# DM0249_IMX378.net
KiCad netlist of a schematic drawn in Altium Designer
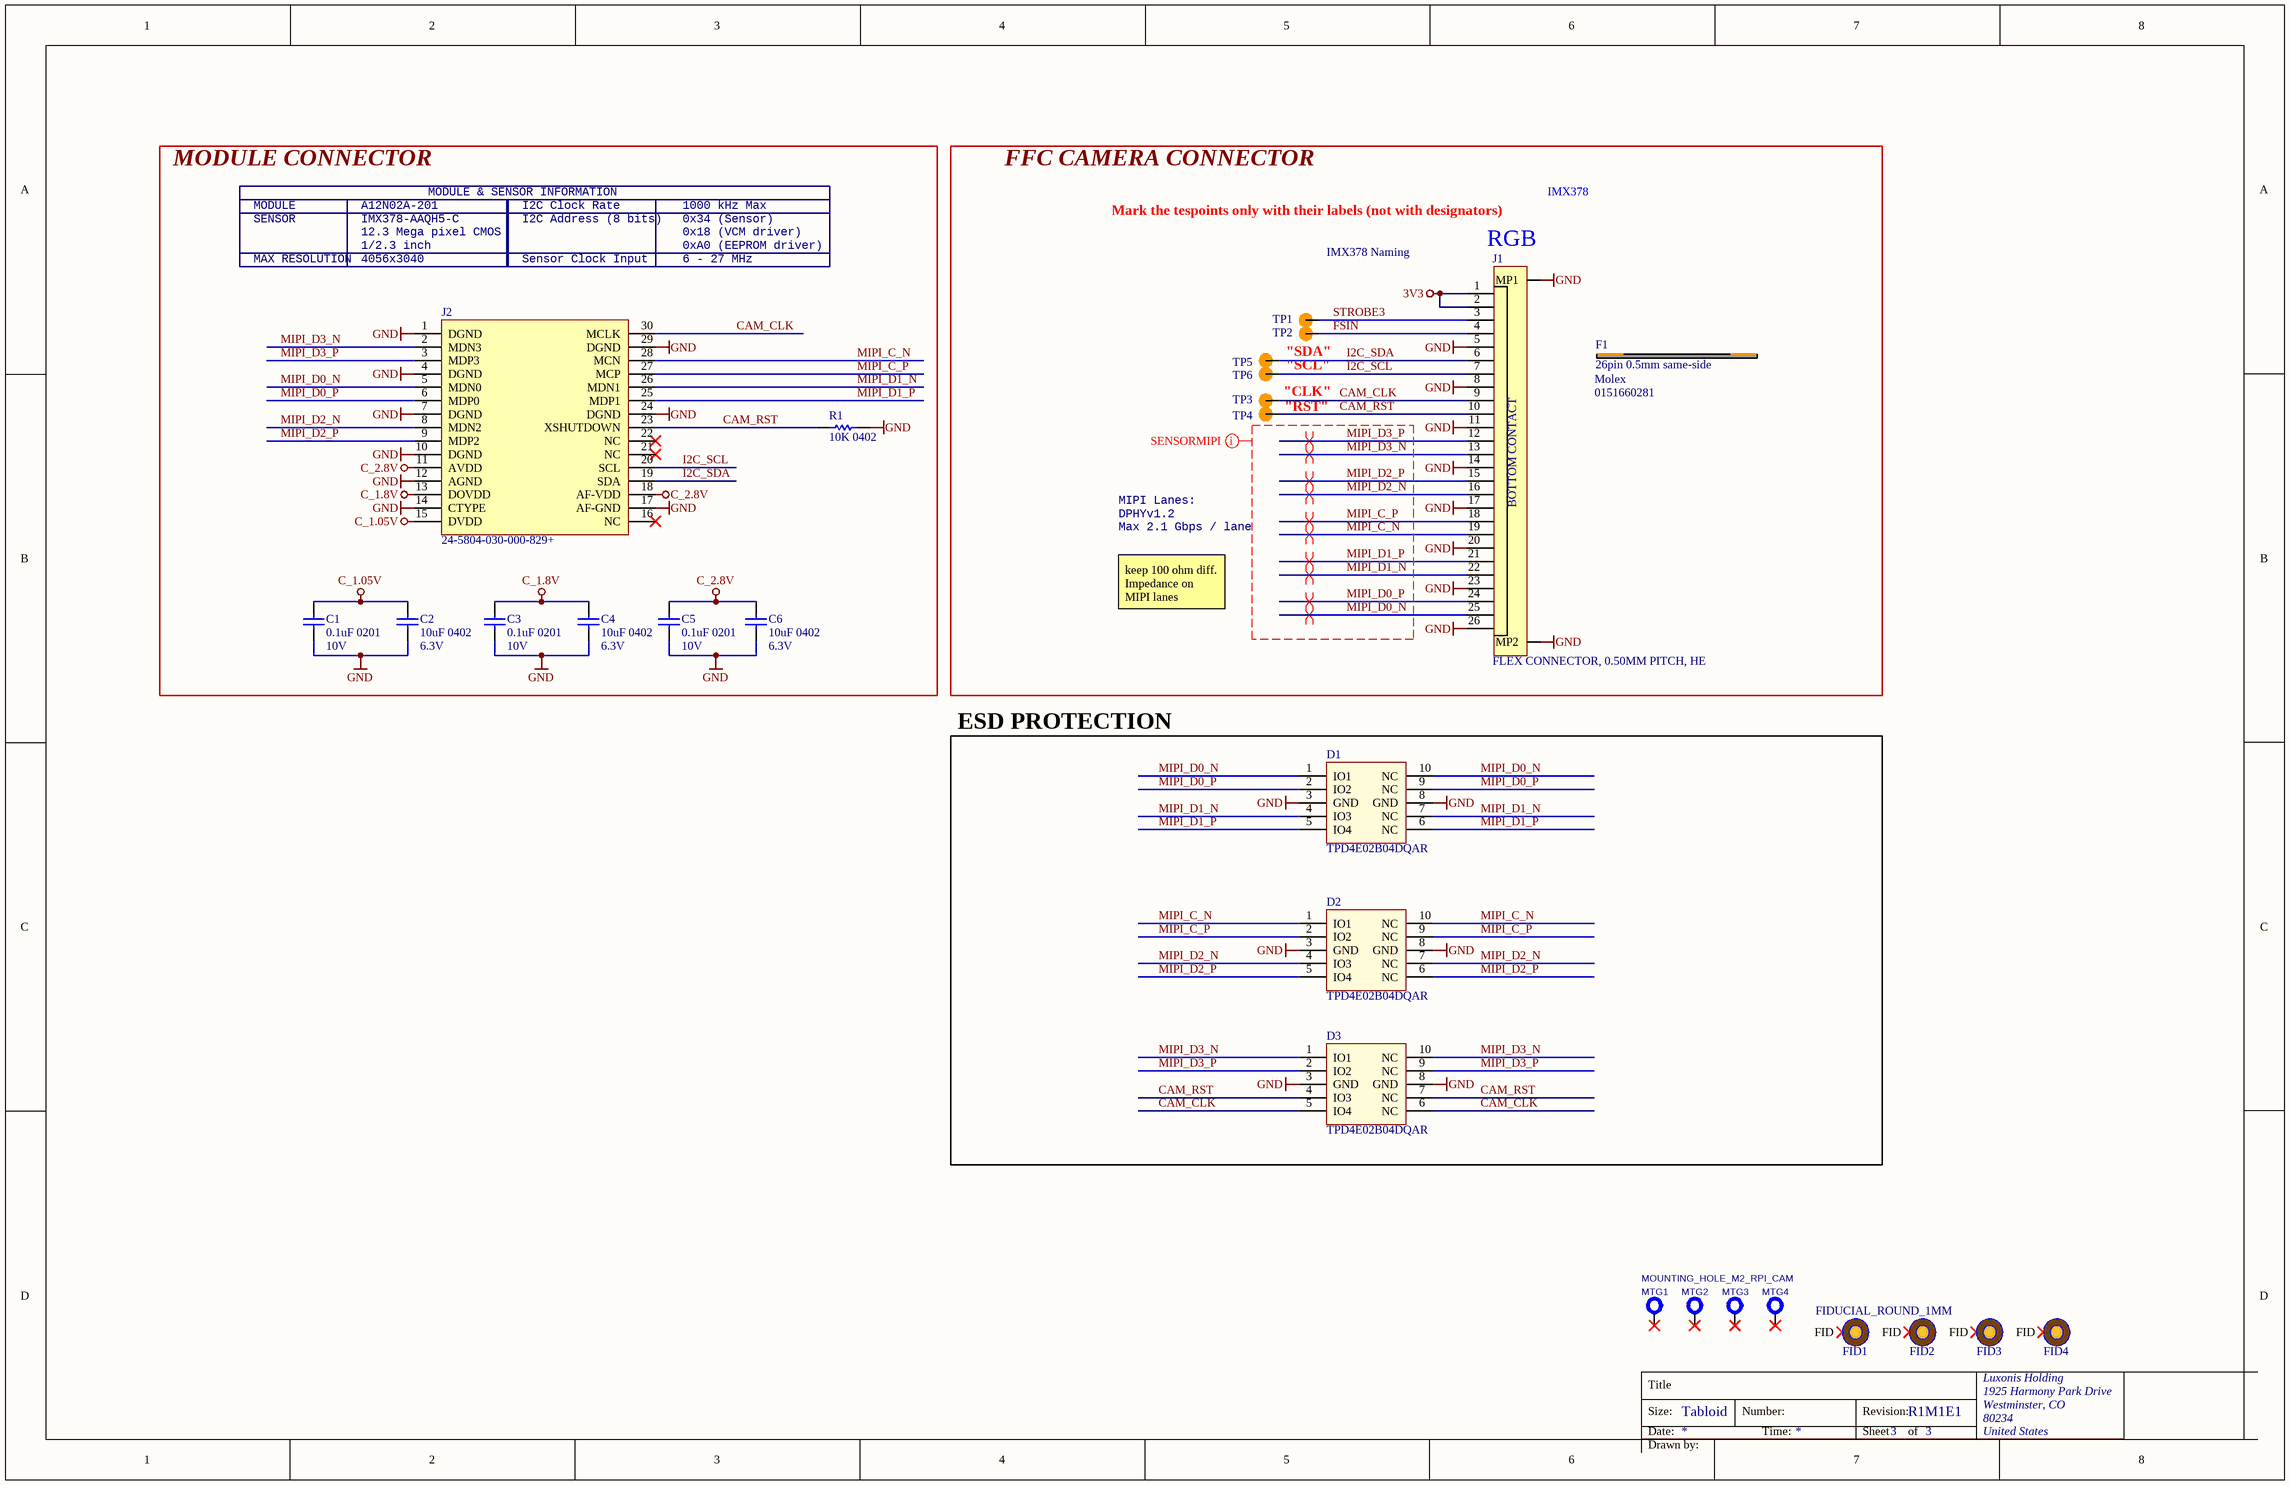
[diagram p0: DM0249_IMX378.SchDoc]

(export (version "E")
  (design (tool "Eeschema 10.0.6"))
  (components
    (comp (ref "C1")
      (value "0.1uF 0201")
      (footprint "CAP_Altium_Vault_Generic:CAPC0201(0603)33_N")
      (description "CAP CER 0.1UF 10V X5R 0201")
      (fields (field (name "TOLERANCE") "10%") (field (name "VOLTAGE") "10V"))
      (libsource (lib "LuxonisMaster") (part "GRM033R61A104KE15D"))
    )
    (comp (ref "C2")
      (value "10uF 0402")
      (footprint "CAP_Altium_Vault_Generic:CAPC0402(1005)70_N")
      (description "CAP CER 10UF 6.3V X5R 0402 20%")
      (fields (field (name "TOLERANCE") "20%") (field (name "VOLTAGE RATING") "6.3V"))
      (libsource (lib "LuxonisMaster") (part "GRM155R60J106ME15D"))
    )
    (comp (ref "C3")
      (value "0.1uF 0201")
      (footprint "CAP_Altium_Vault_Generic:CAPC0201(0603)33_N")
      (description "CAP CER 0.1UF 10V X5R 0201")
      (fields (field (name "TOLERANCE") "10%") (field (name "VOLTAGE") "10V"))
      (libsource (lib "LuxonisMaster") (part "GRM033R61A104KE15D"))
    )
    (comp (ref "C4")
      (value "10uF 0402")
      (footprint "CAP_Altium_Vault_Generic:CAPC0402(1005)70_N")
      (description "CAP CER 10UF 6.3V X5R 0402 20%")
      (fields (field (name "TOLERANCE") "20%") (field (name "VOLTAGE RATING") "6.3V"))
      (libsource (lib "LuxonisMaster") (part "GRM155R60J106ME15D"))
    )
    (comp (ref "C5")
      (value "0.1uF 0201")
      (footprint "CAP_Altium_Vault_Generic:CAPC0201(0603)33_N")
      (description "CAP CER 0.1UF 10V X5R 0201")
      (fields (field (name "TOLERANCE") "10%") (field (name "VOLTAGE") "10V"))
      (libsource (lib "LuxonisMaster") (part "GRM033R61A104KE15D"))
    )
    (comp (ref "C6")
      (value "10uF 0402")
      (footprint "CAP_Altium_Vault_Generic:CAPC0402(1005)70_N")
      (description "CAP CER 10UF 6.3V X5R 0402 20%")
      (fields (field (name "TOLERANCE") "20%") (field (name "VOLTAGE RATING") "6.3V"))
      (libsource (lib "LuxonisMaster") (part "GRM155R60J106ME15D"))
    )
    (comp (ref "D1")
      (value "TPD4E02B04DQAR")
      (footprint "LuxonisMaster:TPD4E02B04DQAR")
      (libsource (lib "LuxonisMaster") (part "TPD4E02B04DQAR"))
    )
    (comp (ref "D2")
      (value "TPD4E02B04DQAR")
      (footprint "LuxonisMaster:TPD4E02B04DQAR")
      (libsource (lib "LuxonisMaster") (part "TPD4E02B04DQAR"))
    )
    (comp (ref "D3")
      (value "TPD4E02B04DQAR")
      (footprint "LuxonisMaster:TPD4E02B04DQAR")
      (libsource (lib "LuxonisMaster") (part "TPD4E02B04DQAR"))
    )
    (comp (ref "F1")
      (value "26pin 0.5mm same-side")
      (description "CABLE FFC 26POS 0.50MM 6\"")
      (fields
        (field (name "MANUFACTURER 1") "Molex")
        (field (name "MANUFACTURER PART NUMBER 1") "0151660281")
      )
      (libsource (lib "BG0249_R1M1E1") (part "0151660281"))
    )
    (comp (ref "FID1")
      (value "FIDUCIAL_ROUND_1MM")
      (footprint "LuxonisMaster:FIDUCIAL_ROUND_1MM")
      (description "Fiducial with various available footprints")
      (libsource (lib "LuxonisMaster") (part "FIDUCIAL"))
    )
    (comp (ref "FID2")
      (value "FIDUCIAL_ROUND_1MM")
      (footprint "LuxonisMaster:FIDUCIAL_ROUND_1MM")
      (description "Fiducial with various available footprints")
      (libsource (lib "LuxonisMaster") (part "FIDUCIAL"))
    )
    (comp (ref "FID3")
      (value "FIDUCIAL_ROUND_1MM")
      (footprint "LuxonisMaster:FIDUCIAL_ROUND_1MM")
      (description "Fiducial with various available footprints")
      (libsource (lib "LuxonisMaster") (part "FIDUCIAL"))
    )
    (comp (ref "FID4")
      (value "FIDUCIAL_ROUND_1MM")
      (footprint "LuxonisMaster:FIDUCIAL_ROUND_1MM")
      (description "Fiducial with various available footprints")
      (libsource (lib "LuxonisMaster") (part "FIDUCIAL"))
    )
    (comp (ref "J1")
      (value "FLEX CONNECTOR, 0.50MM PITCH, HE")
      (footprint "DM1090FFC:F32R-1A7H1-11026")
      (description "26 Position FFC, FPC Connector Contacts, Bottom 0.020\" (0.50mm) Surface Mount, Right Angle")
      (libsource (lib "DM1090FFC") (part "F32R-1A7H1-11026"))
    )
    (comp (ref "J2")
      (value "24-5804-030-000-829+")
      (footprint "LuxonisMaster:A12N02A-201_1.6mmbrd_MatedModule")
      (description "CONN Series 5804 board to board 0.4mm pitch 30 way connector")
      (libsource (lib "LuxonisMaster") (part "A12N02A-201_Connector"))
    )
    (comp (ref "MTG1")
      (value "MOUNTING_HOLE_M2_RPI_CAM")
      (footprint "LuxonisMaster:MOUNTING_HOLE_M2_RPI_CAM")
      (description "=CurrentFootprint")
      (libsource (lib "LuxonisMaster") (part "MP_Mounting-Holes"))
    )
    (comp (ref "MTG2")
      (value "MOUNTING_HOLE_M2_RPI_CAM")
      (footprint "LuxonisMaster:MOUNTING_HOLE_M2_RPI_CAM")
      (description "=CurrentFootprint")
      (libsource (lib "LuxonisMaster") (part "MP_Mounting-Holes"))
    )
    (comp (ref "MTG3")
      (value "MOUNTING_HOLE_M2_RPI_CAM")
      (footprint "LuxonisMaster:MOUNTING_HOLE_M2_RPI_CAM")
      (description "=CurrentFootprint")
      (libsource (lib "LuxonisMaster") (part "MP_Mounting-Holes"))
    )
    (comp (ref "MTG4")
      (value "MOUNTING_HOLE_M2_RPI_CAM")
      (footprint "LuxonisMaster:MOUNTING_HOLE_M2_RPI_CAM")
      (description "=CurrentFootprint")
      (libsource (lib "LuxonisMaster") (part "MP_Mounting-Holes"))
    )
    (comp (ref "R1")
      (value "10K 0402")
      (footprint "RES_Altium_Vault_Generic:RESC0402(1005)_N")
      (fields (field (name "TOLERANCE") "1%"))
      (libsource (lib "LuxonisMaster") (part "RC0402FR-1310KL"))
    )
    (comp (ref "TP1")
      (value "TP100_200_NS")
      (footprint "LuxonisMaster:TP100_200_NS")
      (libsource (lib "LuxonisMaster") (part "TEST_POINT"))
    )
    (comp (ref "TP2")
      (value "TP100_200_NS")
      (footprint "LuxonisMaster:TP100_200_NS")
      (libsource (lib "LuxonisMaster") (part "TEST_POINT"))
    )
    (comp (ref "TP3")
      (value "TP100_200_NS")
      (footprint "LuxonisMaster:TP100_200_NS")
      (libsource (lib "LuxonisMaster") (part "TEST_POINT"))
    )
    (comp (ref "TP4")
      (value "TP100_200_NS")
      (footprint "LuxonisMaster:TP100_200_NS")
      (libsource (lib "LuxonisMaster") (part "TEST_POINT"))
    )
    (comp (ref "TP5")
      (value "TP100_200_NS")
      (footprint "LuxonisMaster:TP100_200_NS")
      (libsource (lib "LuxonisMaster") (part "TEST_POINT"))
    )
    (comp (ref "TP6")
      (value "TP100_200_NS")
      (footprint "LuxonisMaster:TP100_200_NS")
      (libsource (lib "LuxonisMaster") (part "TEST_POINT"))
    )
  )
  (nets
    (net (code "1") (name "/CAM_CLK") (class "Default")
      (node (ref "D3") (pin "5") (pinfunction "IO4_5") (pintype "passive"))
      (node (ref "D3") (pin "6") (pinfunction "NC_6") (pintype "passive"))
      (node (ref "J1") (pin "9") (pinfunction "9_9") (pintype "passive"))
      (node (ref "J2") (pin "30") (pinfunction "MCLK_30") (pintype "passive"))
      (node (ref "TP3") (pin "1") (pintype "passive"))
    )
    (net (code "2") (name "/CAM_RST") (class "Default")
      (node (ref "D3") (pin "4") (pinfunction "IO3_4") (pintype "passive"))
      (node (ref "D3") (pin "7") (pinfunction "NC_7") (pintype "passive"))
      (node (ref "J1") (pin "10") (pinfunction "10_10") (pintype "passive"))
      (node (ref "J2") (pin "23") (pinfunction "XSHUTDOWN_23") (pintype "passive"))
      (node (ref "R1") (pin "1") (pinfunction "1_1") (pintype "passive"))
      (node (ref "TP4") (pin "1") (pintype "passive"))
    )
    (net (code "3") (name "/FSIN") (class "Default")
      (node (ref "J1") (pin "4") (pinfunction "4_4") (pintype "passive"))
      (node (ref "TP2") (pin "1") (pintype "passive"))
    )
    (net (code "4") (name "/I2C_SCL") (class "Default")
      (node (ref "J1") (pin "7") (pinfunction "7_7") (pintype "passive"))
      (node (ref "J2") (pin "20") (pinfunction "SCL_20") (pintype "passive"))
      (node (ref "TP6") (pin "1") (pintype "passive"))
    )
    (net (code "5") (name "/I2C_SDA") (class "Default")
      (node (ref "J1") (pin "6") (pinfunction "6_6") (pintype "passive"))
      (node (ref "J2") (pin "19") (pinfunction "SDA_19") (pintype "passive"))
      (node (ref "TP5") (pin "1") (pintype "passive"))
    )
    (net (code "6") (name "/MIPI_C_N") (class "Default")
      (node (ref "D2") (pin "1") (pinfunction "IO1_1") (pintype "passive"))
      (node (ref "D2") (pin "10") (pinfunction "NC_10") (pintype "passive"))
      (node (ref "J1") (pin "19") (pinfunction "19_19") (pintype "passive"))
      (node (ref "J2") (pin "28") (pinfunction "MCN_28") (pintype "passive"))
    )
    (net (code "7") (name "/MIPI_C_P") (class "Default")
      (node (ref "D2") (pin "2") (pinfunction "IO2_2") (pintype "passive"))
      (node (ref "D2") (pin "9") (pinfunction "NC_9") (pintype "passive"))
      (node (ref "J1") (pin "18") (pinfunction "18_18") (pintype "passive"))
      (node (ref "J2") (pin "27") (pinfunction "MCP_27") (pintype "passive"))
    )
    (net (code "8") (name "/MIPI_D0_N") (class "Default")
      (node (ref "D1") (pin "1") (pinfunction "IO1_1") (pintype "passive"))
      (node (ref "D1") (pin "10") (pinfunction "NC_10") (pintype "passive"))
      (node (ref "J1") (pin "25") (pinfunction "25_25") (pintype "passive"))
      (node (ref "J2") (pin "5") (pinfunction "MDN0_5") (pintype "passive"))
    )
    (net (code "9") (name "/MIPI_D0_P") (class "Default")
      (node (ref "D1") (pin "2") (pinfunction "IO2_2") (pintype "passive"))
      (node (ref "D1") (pin "9") (pinfunction "NC_9") (pintype "passive"))
      (node (ref "J1") (pin "24") (pinfunction "24_24") (pintype "passive"))
      (node (ref "J2") (pin "6") (pinfunction "MDP0_6") (pintype "passive"))
    )
    (net (code "10") (name "/MIPI_D1_N") (class "Default")
      (node (ref "D1") (pin "4") (pinfunction "IO3_4") (pintype "passive"))
      (node (ref "D1") (pin "7") (pinfunction "NC_7") (pintype "passive"))
      (node (ref "J1") (pin "22") (pinfunction "22_22") (pintype "passive"))
      (node (ref "J2") (pin "26") (pinfunction "MDN1_26") (pintype "passive"))
    )
    (net (code "11") (name "/MIPI_D1_P") (class "Default")
      (node (ref "D1") (pin "5") (pinfunction "IO4_5") (pintype "passive"))
      (node (ref "D1") (pin "6") (pinfunction "NC_6") (pintype "passive"))
      (node (ref "J1") (pin "21") (pinfunction "21_21") (pintype "passive"))
      (node (ref "J2") (pin "25") (pinfunction "MDP1_25") (pintype "passive"))
    )
    (net (code "12") (name "/MIPI_D2_N") (class "Default")
      (node (ref "D2") (pin "4") (pinfunction "IO3_4") (pintype "passive"))
      (node (ref "D2") (pin "7") (pinfunction "NC_7") (pintype "passive"))
      (node (ref "J1") (pin "16") (pinfunction "16_16") (pintype "passive"))
      (node (ref "J2") (pin "8") (pinfunction "MDN2_8") (pintype "passive"))
    )
    (net (code "13") (name "/MIPI_D2_P") (class "Default")
      (node (ref "D2") (pin "5") (pinfunction "IO4_5") (pintype "passive"))
      (node (ref "D2") (pin "6") (pinfunction "NC_6") (pintype "passive"))
      (node (ref "J1") (pin "15") (pinfunction "15_15") (pintype "passive"))
      (node (ref "J2") (pin "9") (pinfunction "MDP2_9") (pintype "passive"))
    )
    (net (code "14") (name "/MIPI_D3_N") (class "Default")
      (node (ref "D3") (pin "1") (pinfunction "IO1_1") (pintype "passive"))
      (node (ref "D3") (pin "10") (pinfunction "NC_10") (pintype "passive"))
      (node (ref "J1") (pin "13") (pinfunction "13_13") (pintype "passive"))
      (node (ref "J2") (pin "2") (pinfunction "MDN3_2") (pintype "passive"))
    )
    (net (code "15") (name "/MIPI_D3_P") (class "Default")
      (node (ref "D3") (pin "2") (pinfunction "IO2_2") (pintype "passive"))
      (node (ref "D3") (pin "9") (pinfunction "NC_9") (pintype "passive"))
      (node (ref "J1") (pin "12") (pinfunction "12_12") (pintype "passive"))
      (node (ref "J2") (pin "3") (pinfunction "MDP3_3") (pintype "passive"))
    )
    (net (code "16") (name "/STROBE3") (class "Default")
      (node (ref "J1") (pin "3") (pinfunction "3_3") (pintype "passive"))
      (node (ref "TP1") (pin "1") (pintype "passive"))
    )
    (net (code "17") (name "3V3") (class "Default")
      (node (ref "J1") (pin "1") (pinfunction "1_1") (pintype "passive"))
      (node (ref "J1") (pin "2") (pinfunction "2_2") (pintype "passive"))
    )
    (net (code "18") (name "C_1.05V") (class "Default")
      (node (ref "C1") (pin "2") (pinfunction "2_2") (pintype "passive"))
      (node (ref "C2") (pin "2") (pinfunction "2_2") (pintype "passive"))
      (node (ref "J2") (pin "15") (pinfunction "DVDD_15") (pintype "passive"))
    )
    (net (code "19") (name "C_1.8V") (class "Default")
      (node (ref "C3") (pin "2") (pinfunction "2_2") (pintype "passive"))
      (node (ref "C4") (pin "2") (pinfunction "2_2") (pintype "passive"))
      (node (ref "J2") (pin "13") (pinfunction "DOVDD_13") (pintype "passive"))
    )
    (net (code "20") (name "C_2.8V") (class "Default")
      (node (ref "C5") (pin "2") (pinfunction "2_2") (pintype "passive"))
      (node (ref "C6") (pin "2") (pinfunction "2_2") (pintype "passive"))
      (node (ref "J2") (pin "11") (pinfunction "AVDD_11") (pintype "passive"))
      (node (ref "J2") (pin "18") (pinfunction "AF-VDD_18") (pintype "passive"))
    )
    (net (code "21") (name "GND") (class "Default")
      (node (ref "C1") (pin "1") (pinfunction "1_1") (pintype "passive"))
      (node (ref "C2") (pin "1") (pinfunction "1_1") (pintype "passive"))
      (node (ref "C3") (pin "1") (pinfunction "1_1") (pintype "passive"))
      (node (ref "C4") (pin "1") (pinfunction "1_1") (pintype "passive"))
      (node (ref "C5") (pin "1") (pinfunction "1_1") (pintype "passive"))
      (node (ref "C6") (pin "1") (pinfunction "1_1") (pintype "passive"))
      (node (ref "D1") (pin "3") (pinfunction "GND_3") (pintype "passive"))
      (node (ref "D1") (pin "8") (pinfunction "GND_8") (pintype "passive"))
      (node (ref "D2") (pin "3") (pinfunction "GND_3") (pintype "passive"))
      (node (ref "D2") (pin "8") (pinfunction "GND_8") (pintype "passive"))
      (node (ref "D3") (pin "3") (pinfunction "GND_3") (pintype "passive"))
      (node (ref "D3") (pin "8") (pinfunction "GND_8") (pintype "passive"))
      (node (ref "J1") (pin "11") (pinfunction "11_11") (pintype "passive"))
      (node (ref "J1") (pin "14") (pinfunction "14_14") (pintype "passive"))
      (node (ref "J1") (pin "17") (pinfunction "17_17") (pintype "passive"))
      (node (ref "J1") (pin "20") (pinfunction "20_20") (pintype "passive"))
      (node (ref "J1") (pin "23") (pinfunction "23_23") (pintype "passive"))
      (node (ref "J1") (pin "26") (pinfunction "26_26") (pintype "passive"))
      (node (ref "J1") (pin "5") (pinfunction "5_5") (pintype "passive"))
      (node (ref "J1") (pin "8") (pinfunction "8_8") (pintype "passive"))
      (node (ref "J1") (pin "MP1") (pinfunction "MP1_MP1") (pintype "passive"))
      (node (ref "J1") (pin "MP2") (pinfunction "MP2_MP2") (pintype "passive"))
      (node (ref "J2") (pin "1") (pinfunction "DGND_1") (pintype "passive"))
      (node (ref "J2") (pin "10") (pinfunction "DGND_10") (pintype "passive"))
      (node (ref "J2") (pin "12") (pinfunction "AGND_12") (pintype "passive"))
      (node (ref "J2") (pin "14") (pinfunction "CTYPE_14") (pintype "passive"))
      (node (ref "J2") (pin "17") (pinfunction "AF-GND_17") (pintype "passive"))
      (node (ref "J2") (pin "24") (pinfunction "DGND_24") (pintype "passive"))
      (node (ref "J2") (pin "29") (pinfunction "DGND_29") (pintype "passive"))
      (node (ref "J2") (pin "4") (pinfunction "DGND_4") (pintype "passive"))
      (node (ref "J2") (pin "7") (pinfunction "DGND_7") (pintype "passive"))
      (node (ref "R1") (pin "2") (pinfunction "2_2") (pintype "passive"))
    )
    (net (code "22") (name "unconnected-(FID1-PadFID)") (class "Default")
      (node (ref "FID1") (pin "FID") (pinfunction "FID_FID") (pintype "input+no_connect"))
    )
    (net (code "23") (name "unconnected-(FID2-PadFID)") (class "Default")
      (node (ref "FID2") (pin "FID") (pinfunction "FID_FID") (pintype "input+no_connect"))
    )
    (net (code "24") (name "unconnected-(FID3-PadFID)") (class "Default")
      (node (ref "FID3") (pin "FID") (pinfunction "FID_FID") (pintype "input+no_connect"))
    )
    (net (code "25") (name "unconnected-(FID4-PadFID)") (class "Default")
      (node (ref "FID4") (pin "FID") (pinfunction "FID_FID") (pintype "input+no_connect"))
    )
    (net (code "26") (name "unconnected-(J2-NC-Pad16)") (class "Default")
      (node (ref "J2") (pin "16") (pinfunction "NC_16") (pintype "passive+no_connect"))
    )
    (net (code "27") (name "unconnected-(J2-NC-Pad21)") (class "Default")
      (node (ref "J2") (pin "21") (pinfunction "NC_21") (pintype "passive+no_connect"))
    )
    (net (code "28") (name "unconnected-(J2-NC-Pad22)") (class "Default")
      (node (ref "J2") (pin "22") (pinfunction "NC_22") (pintype "passive+no_connect"))
    )
    (net (code "29") (name "unconnected-(MTG1-Pad1)") (class "Default")
      (node (ref "MTG1") (pin "1") (pintype "passive+no_connect"))
    )
    (net (code "30") (name "unconnected-(MTG2-Pad1)") (class "Default")
      (node (ref "MTG2") (pin "1") (pintype "passive+no_connect"))
    )
    (net (code "31") (name "unconnected-(MTG3-Pad1)") (class "Default")
      (node (ref "MTG3") (pin "1") (pintype "passive+no_connect"))
    )
    (net (code "32") (name "unconnected-(MTG4-Pad1)") (class "Default")
      (node (ref "MTG4") (pin "1") (pintype "passive+no_connect"))
    )
  )
)
